# tqfp_0_8mm_breakout.net
KiCad netlist of a schematic drawn in EAGLE
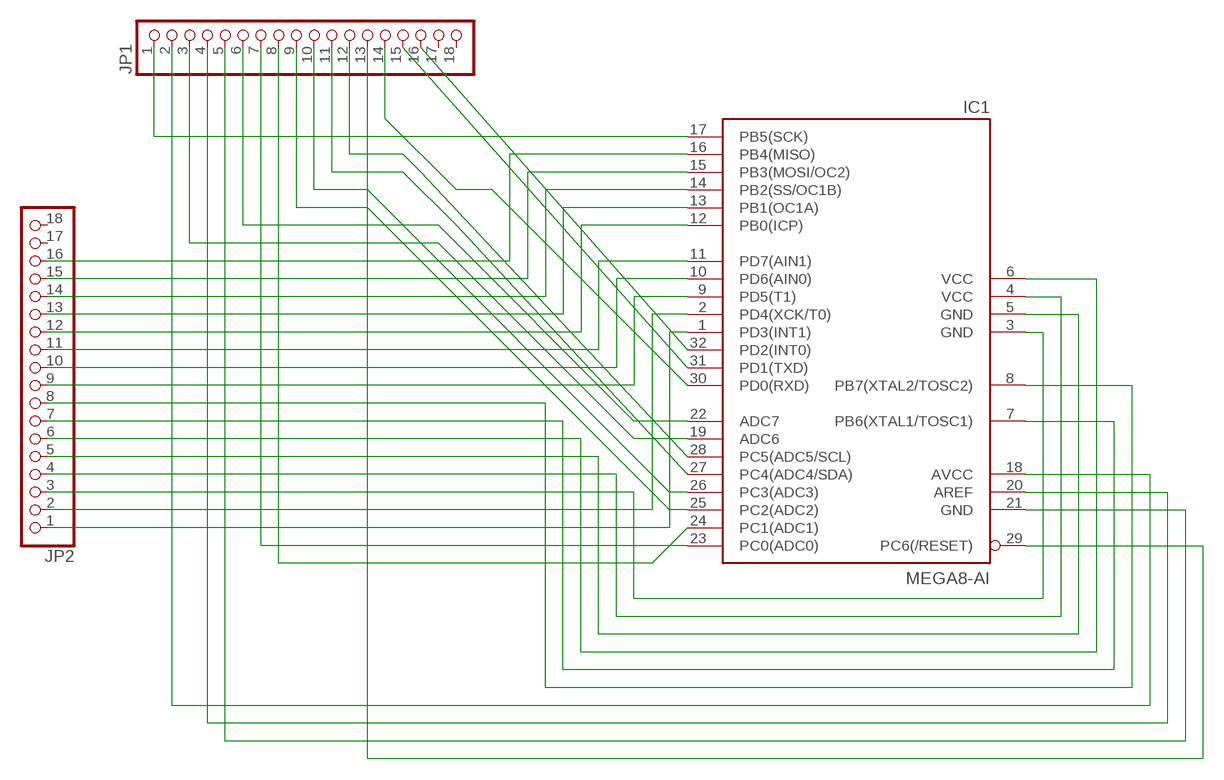
[diagram p0: schematic, sheet 1]

(export (version "E")
  (design (tool "Eeschema 10.0.6"))
  (components
    (comp (ref "IC1")
      (value "MEGA8-AI")
      (footprint "eagle-import:TQFP32-08")
      (fields (field (name "MPN") "ATMEGA8-16AU"))
      (libsource (lib "eagle-import") (part "MEGA8-AI"))
    )
    (comp (ref "JP1")
      (value "PINHD-1X18")
      (footprint "eagle-import:1X18")
      (libsource (lib "eagle-import") (part "PINHD-1X18"))
    )
    (comp (ref "JP2")
      (value "PINHD-1X18")
      (footprint "eagle-import:1X18")
      (libsource (lib "eagle-import") (part "PINHD-1X18"))
    )
  )
  (nets
    (net (code "1") (name "Net-(IC1-ADC6)") (class "Default")
      (node (ref "IC1") (pin "19") (pinfunction "ADC6_19") (pintype "bidirectional"))
      (node (ref "JP1") (pin "3") (pinfunction "3_3") (pintype "passive"))
    )
    (net (code "2") (name "Net-(IC1-ADC7)") (class "Default")
      (node (ref "IC1") (pin "22") (pinfunction "ADC7_22") (pintype "bidirectional"))
      (node (ref "JP1") (pin "6") (pinfunction "6_6") (pintype "passive"))
    )
    (net (code "3") (name "Net-(IC1-AREF)") (class "Default")
      (node (ref "IC1") (pin "20") (pinfunction "AREF_20") (pintype "passive"))
      (node (ref "JP1") (pin "4") (pinfunction "4_4") (pintype "passive"))
    )
    (net (code "4") (name "Net-(IC1-AVCC)") (class "Default")
      (node (ref "IC1") (pin "18") (pinfunction "AVCC_18") (pintype "power_in"))
      (node (ref "JP1") (pin "2") (pinfunction "2_2") (pintype "passive"))
    )
    (net (code "5") (name "Net-(IC1-GND-Pad3)") (class "Default")
      (node (ref "IC1") (pin "3") (pinfunction "GND_3") (pintype "power_in"))
      (node (ref "JP2") (pin "3") (pinfunction "3_3") (pintype "passive"))
    )
    (net (code "6") (name "Net-(IC1-GND-Pad5)") (class "Default")
      (node (ref "IC1") (pin "5") (pinfunction "GND_5") (pintype "power_in"))
      (node (ref "JP2") (pin "5") (pinfunction "5_5") (pintype "passive"))
    )
    (net (code "7") (name "Net-(IC1-GND-Pad21)") (class "Default")
      (node (ref "IC1") (pin "21") (pinfunction "GND_21") (pintype "power_in"))
      (node (ref "JP1") (pin "5") (pinfunction "5_5") (pintype "passive"))
    )
    (net (code "8") (name "Net-(IC1-PB0(ICP))") (class "Default")
      (node (ref "IC1") (pin "12") (pinfunction "PB0(ICP)_12") (pintype "bidirectional"))
      (node (ref "JP2") (pin "12") (pinfunction "12_12") (pintype "passive"))
    )
    (net (code "9") (name "Net-(IC1-PB1(OC1A))") (class "Default")
      (node (ref "IC1") (pin "13") (pinfunction "PB1(OC1A)_13") (pintype "bidirectional"))
      (node (ref "JP2") (pin "13") (pinfunction "13_13") (pintype "passive"))
    )
    (net (code "10") (name "Net-(IC1-PB2(SS{slash}OC1B))") (class "Default")
      (node (ref "IC1") (pin "14") (pinfunction "PB2(SS/OC1B)_14") (pintype "bidirectional"))
      (node (ref "JP2") (pin "14") (pinfunction "14_14") (pintype "passive"))
    )
    (net (code "11") (name "Net-(IC1-PB3(MOSI{slash}OC2))") (class "Default")
      (node (ref "IC1") (pin "15") (pinfunction "PB3(MOSI/OC2)_15") (pintype "bidirectional"))
      (node (ref "JP2") (pin "15") (pinfunction "15_15") (pintype "passive"))
    )
    (net (code "12") (name "Net-(IC1-PB4(MISO))") (class "Default")
      (node (ref "IC1") (pin "16") (pinfunction "PB4(MISO)_16") (pintype "bidirectional"))
      (node (ref "JP2") (pin "16") (pinfunction "16_16") (pintype "passive"))
    )
    (net (code "13") (name "Net-(IC1-PB5(SCK))") (class "Default")
      (node (ref "IC1") (pin "17") (pinfunction "PB5(SCK)_17") (pintype "bidirectional"))
      (node (ref "JP1") (pin "1") (pinfunction "1_1") (pintype "passive"))
    )
    (net (code "14") (name "Net-(IC1-PB6(XTAL1{slash}TOSC1))") (class "Default")
      (node (ref "IC1") (pin "7") (pinfunction "PB6(XTAL1/TOSC1)_7") (pintype "bidirectional"))
      (node (ref "JP2") (pin "7") (pinfunction "7_7") (pintype "passive"))
    )
    (net (code "15") (name "Net-(IC1-PB7(XTAL2{slash}TOSC2))") (class "Default")
      (node (ref "IC1") (pin "8") (pinfunction "PB7(XTAL2/TOSC2)_8") (pintype "bidirectional"))
      (node (ref "JP2") (pin "8") (pinfunction "8_8") (pintype "passive"))
    )
    (net (code "16") (name "Net-(IC1-PC0(ADC0))") (class "Default")
      (node (ref "IC1") (pin "23") (pinfunction "PC0(ADC0)_23") (pintype "bidirectional"))
      (node (ref "JP1") (pin "7") (pinfunction "7_7") (pintype "passive"))
    )
    (net (code "17") (name "Net-(IC1-PC1(ADC1))") (class "Default")
      (node (ref "IC1") (pin "24") (pinfunction "PC1(ADC1)_24") (pintype "bidirectional"))
      (node (ref "JP1") (pin "8") (pinfunction "8_8") (pintype "passive"))
    )
    (net (code "18") (name "Net-(IC1-PC2(ADC2))") (class "Default")
      (node (ref "IC1") (pin "25") (pinfunction "PC2(ADC2)_25") (pintype "bidirectional"))
      (node (ref "JP1") (pin "9") (pinfunction "9_9") (pintype "passive"))
    )
    (net (code "19") (name "Net-(IC1-PC3(ADC3))") (class "Default")
      (node (ref "IC1") (pin "26") (pinfunction "PC3(ADC3)_26") (pintype "bidirectional"))
      (node (ref "JP1") (pin "10") (pinfunction "10_10") (pintype "passive"))
    )
    (net (code "20") (name "Net-(IC1-PC4(ADC4{slash}SDA))") (class "Default")
      (node (ref "IC1") (pin "27") (pinfunction "PC4(ADC4/SDA)_27") (pintype "bidirectional"))
      (node (ref "JP1") (pin "11") (pinfunction "11_11") (pintype "passive"))
    )
    (net (code "21") (name "Net-(IC1-PC5(ADC5{slash}SCL))") (class "Default")
      (node (ref "IC1") (pin "28") (pinfunction "PC5(ADC5/SCL)_28") (pintype "bidirectional"))
      (node (ref "JP1") (pin "12") (pinfunction "12_12") (pintype "passive"))
    )
    (net (code "22") (name "Net-(IC1-PC6({slash}RESET))") (class "Default")
      (node (ref "IC1") (pin "29") (pinfunction "PC6(/RESET)_29") (pintype "bidirectional"))
      (node (ref "JP1") (pin "13") (pinfunction "13_13") (pintype "passive"))
    )
    (net (code "23") (name "Net-(IC1-PD0(RXD))") (class "Default")
      (node (ref "IC1") (pin "30") (pinfunction "PD0(RXD)_30") (pintype "bidirectional"))
      (node (ref "JP1") (pin "14") (pinfunction "14_14") (pintype "passive"))
    )
    (net (code "24") (name "Net-(IC1-PD1(TXD))") (class "Default")
      (node (ref "IC1") (pin "31") (pinfunction "PD1(TXD)_31") (pintype "bidirectional"))
      (node (ref "JP1") (pin "15") (pinfunction "15_15") (pintype "passive"))
    )
    (net (code "25") (name "Net-(IC1-PD2(INT0))") (class "Default")
      (node (ref "IC1") (pin "32") (pinfunction "PD2(INT0)_32") (pintype "bidirectional"))
      (node (ref "JP1") (pin "16") (pinfunction "16_16") (pintype "passive"))
    )
    (net (code "26") (name "Net-(IC1-PD3(INT1))") (class "Default")
      (node (ref "IC1") (pin "1") (pinfunction "PD3(INT1)_1") (pintype "bidirectional"))
      (node (ref "JP2") (pin "1") (pinfunction "1_1") (pintype "passive"))
    )
    (net (code "27") (name "Net-(IC1-PD4(XCK{slash}T0))") (class "Default")
      (node (ref "IC1") (pin "2") (pinfunction "PD4(XCK/T0)_2") (pintype "bidirectional"))
      (node (ref "JP2") (pin "2") (pinfunction "2_2") (pintype "passive"))
    )
    (net (code "28") (name "Net-(IC1-PD5(T1))") (class "Default")
      (node (ref "IC1") (pin "9") (pinfunction "PD5(T1)_9") (pintype "bidirectional"))
      (node (ref "JP2") (pin "9") (pinfunction "9_9") (pintype "passive"))
    )
    (net (code "29") (name "Net-(IC1-PD6(AIN0))") (class "Default")
      (node (ref "IC1") (pin "10") (pinfunction "PD6(AIN0)_10") (pintype "bidirectional"))
      (node (ref "JP2") (pin "10") (pinfunction "10_10") (pintype "passive"))
    )
    (net (code "30") (name "Net-(IC1-PD7(AIN1))") (class "Default")
      (node (ref "IC1") (pin "11") (pinfunction "PD7(AIN1)_11") (pintype "bidirectional"))
      (node (ref "JP2") (pin "11") (pinfunction "11_11") (pintype "passive"))
    )
    (net (code "31") (name "Net-(IC1-VCC-Pad4)") (class "Default")
      (node (ref "IC1") (pin "4") (pinfunction "VCC_4") (pintype "power_in"))
      (node (ref "JP2") (pin "4") (pinfunction "4_4") (pintype "passive"))
    )
    (net (code "32") (name "Net-(IC1-VCC-Pad6)") (class "Default")
      (node (ref "IC1") (pin "6") (pinfunction "VCC_6") (pintype "power_in"))
      (node (ref "JP2") (pin "6") (pinfunction "6_6") (pintype "passive"))
    )
    (net (code "33") (name "unconnected-(JP1-Pad17)") (class "Default")
      (node (ref "JP1") (pin "17") (pinfunction "17_17") (pintype "passive"))
    )
    (net (code "34") (name "unconnected-(JP1-Pad18)") (class "Default")
      (node (ref "JP1") (pin "18") (pinfunction "18_18") (pintype "passive"))
    )
    (net (code "35") (name "unconnected-(JP2-Pad17)") (class "Default")
      (node (ref "JP2") (pin "17") (pinfunction "17_17") (pintype "passive"))
    )
    (net (code "36") (name "unconnected-(JP2-Pad18)") (class "Default")
      (node (ref "JP2") (pin "18") (pinfunction "18_18") (pintype "passive"))
    )
  )
)
